# MyoWare_Power_Shield.net
KiCad netlist of a schematic drawn in EAGLE
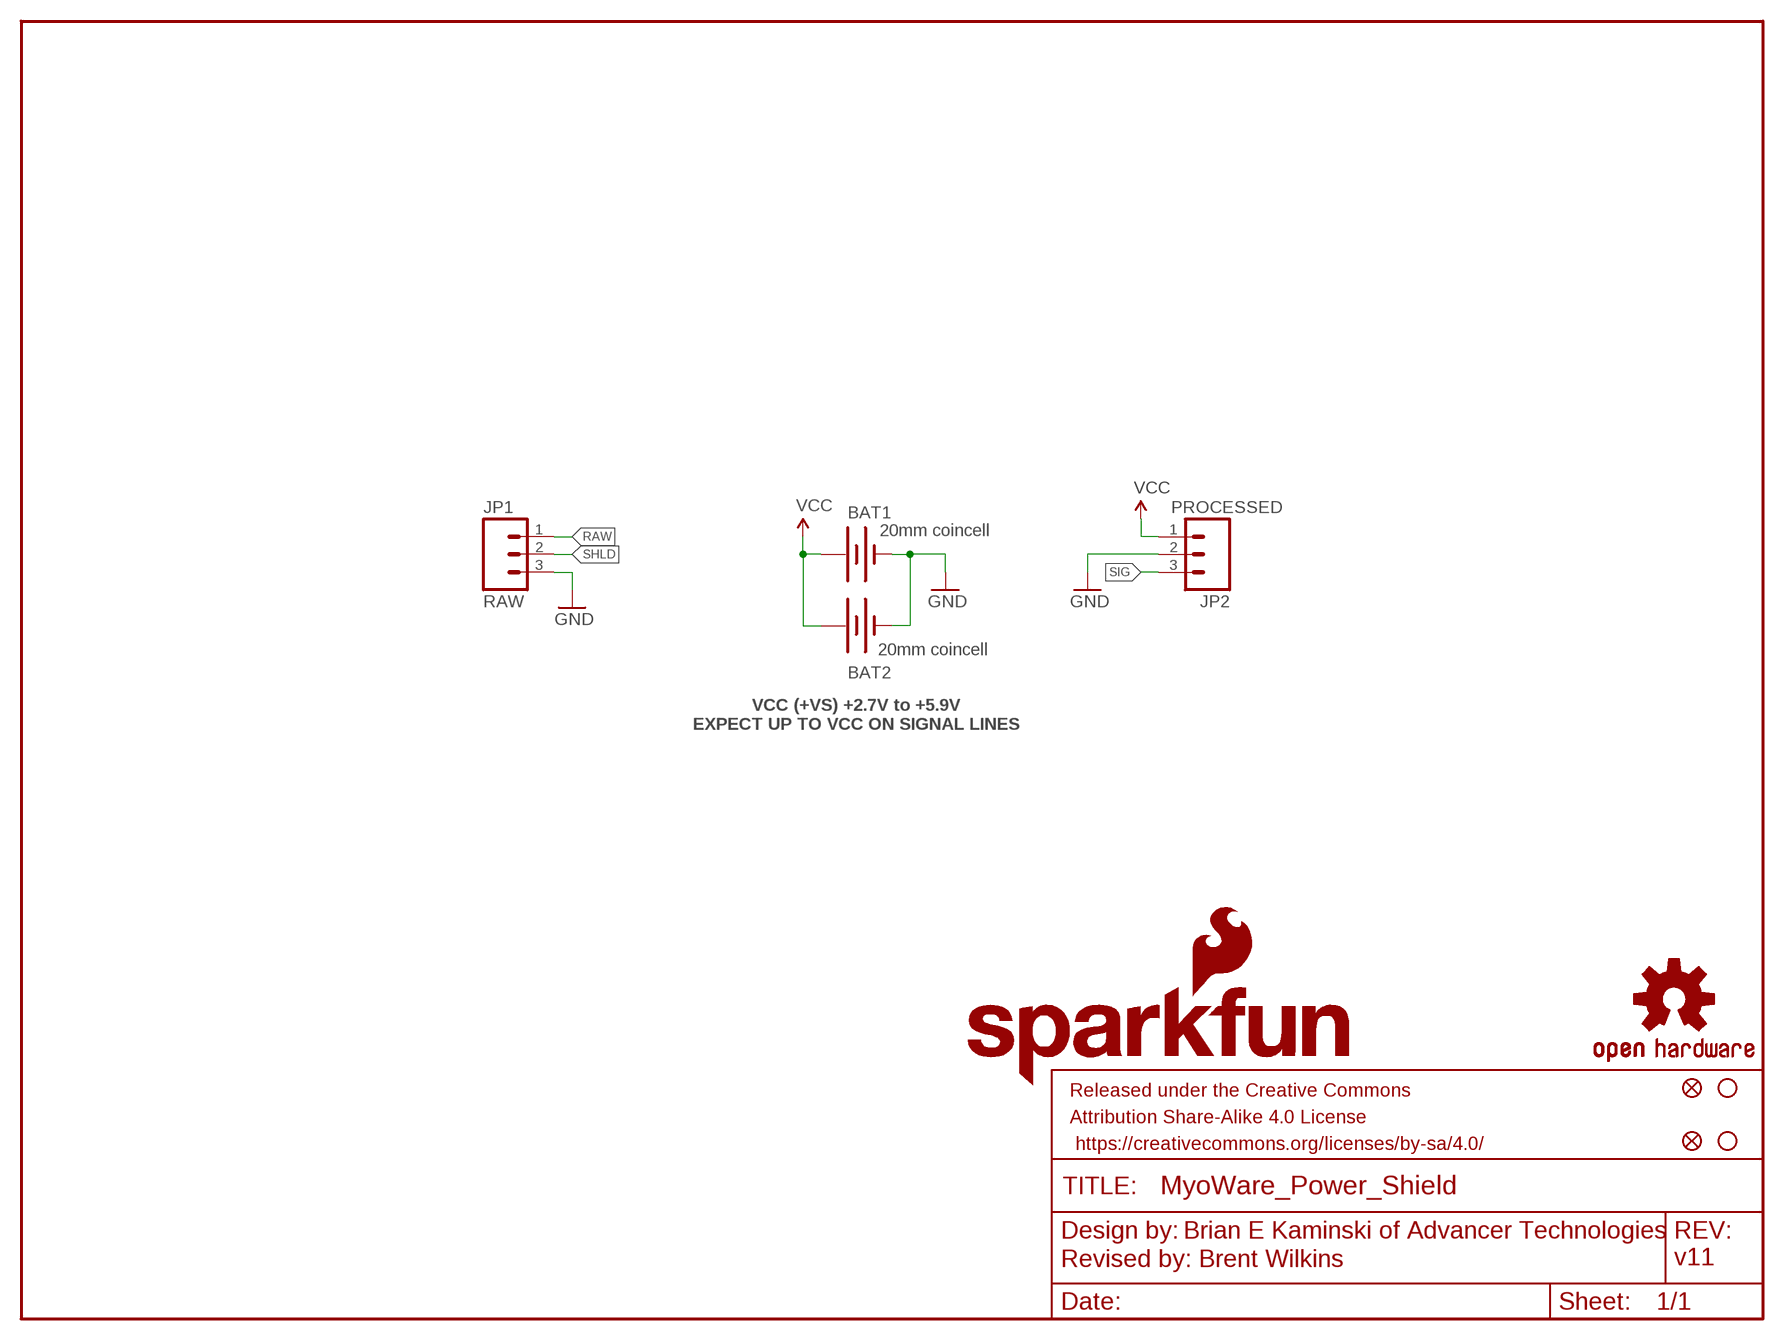
[diagram p0: schematic, sheet 1]

(export (version "E")
  (design (tool "Eeschema 10.0.6"))
  (components
    (comp (ref "BAT1")
      (value "20mm coincell")
      (footprint "eagle-import:BATTCON_20MM_4LEGS")
      (fields (field (name "PROD_ID") "BATT-10373"))
      (libsource (lib "eagle-import") (part "BATTERY20MM_4LEGS"))
    )
    (comp (ref "BAT2")
      (value "20mm coincell")
      (footprint "eagle-import:BATTCON_20MM_4LEGS")
      (fields (field (name "PROD_ID") "BATT-10373"))
      (libsource (lib "eagle-import") (part "BATTERY20MM_4LEGS"))
    )
    (comp (ref "FID1")
      (value "FIDUCIAL1X2")
      (footprint "eagle-import:FIDUCIAL-1X2")
      (libsource (lib "eagle-import") (part "FIDUCIAL1X2"))
    )
    (comp (ref "FID2")
      (value "FIDUCIAL1X2")
      (footprint "eagle-import:FIDUCIAL-1X2")
      (libsource (lib "eagle-import") (part "FIDUCIAL1X2"))
    )
    (comp (ref "FRAME1")
      (value "FRAME-LETTER")
      (footprint "eagle-import:CREATIVE_COMMONS")
      (libsource (lib "eagle-import") (part "FRAME-LETTER"))
    )
    (comp (ref "JP1")
      (value "RAW")
      (footprint "eagle-import:1X03_NO_SILK")
      (libsource (lib "eagle-import") (part "M03ALT_ORDER"))
    )
    (comp (ref "JP2")
      (value "PROCESSED")
      (footprint "eagle-import:1X03_NO_SILK")
      (libsource (lib "eagle-import") (part "M031X03_NO_SILK"))
    )
    (comp (ref "JP3")
      (value "STAND-OFF")
      (footprint "eagle-import:STAND-OFF")
      (libsource (lib "eagle-import") (part "STAND-OFF"))
    )
    (comp (ref "JP4")
      (value "STAND-OFF")
      (footprint "eagle-import:STAND-OFF")
      (libsource (lib "eagle-import") (part "STAND-OFF"))
    )
    (comp (ref "LOGO1")
      (value "SFE_LOGO_NAME_FLAME.1_INCH")
      (footprint "eagle-import:SFE_LOGO_NAME_FLAME_.1")
      (libsource (lib "eagle-import") (part "SFE_LOGO_NAME_FLAME.1_INCH"))
    )
    (comp (ref "LOGO2")
      (value "OSHW-LOGOM")
      (footprint "eagle-import:OSHW-LOGO-M")
      (libsource (lib "eagle-import") (part "OSHW-LOGOM"))
    )
  )
  (nets
    (net (code "1") (name "GND") (class "Default")
      (node (ref "BAT1") (pin "2") (pinfunction "-_2") (pintype "power_in"))
      (node (ref "BAT2") (pin "2") (pinfunction "-_2") (pintype "power_in"))
      (node (ref "JP1") (pin "3") (pinfunction "1_3") (pintype "passive"))
      (node (ref "JP2") (pin "2") (pinfunction "2_2") (pintype "passive"))
    )
    (net (code "2") (name "RAW") (class "Default")
      (node (ref "JP1") (pin "1") (pinfunction "3_1") (pintype "passive"))
    )
    (net (code "3") (name "SHLD") (class "Default")
      (node (ref "JP1") (pin "2") (pinfunction "2_2") (pintype "passive"))
    )
    (net (code "4") (name "SIG") (class "Default")
      (node (ref "JP2") (pin "3") (pinfunction "3_3") (pintype "passive"))
    )
    (net (code "5") (name "VCC") (class "Default")
      (node (ref "BAT1") (pin "1") (pinfunction "+_1") (pintype "power_in"))
      (node (ref "BAT2") (pin "1") (pinfunction "+_1") (pintype "power_in"))
      (node (ref "JP2") (pin "1") (pinfunction "1_1") (pintype "passive"))
    )
  )
)
